# Capacitive-Fluid-Level-Sensor-schematic.net
KiCad netlist of a schematic drawn in EasyEDA Pro
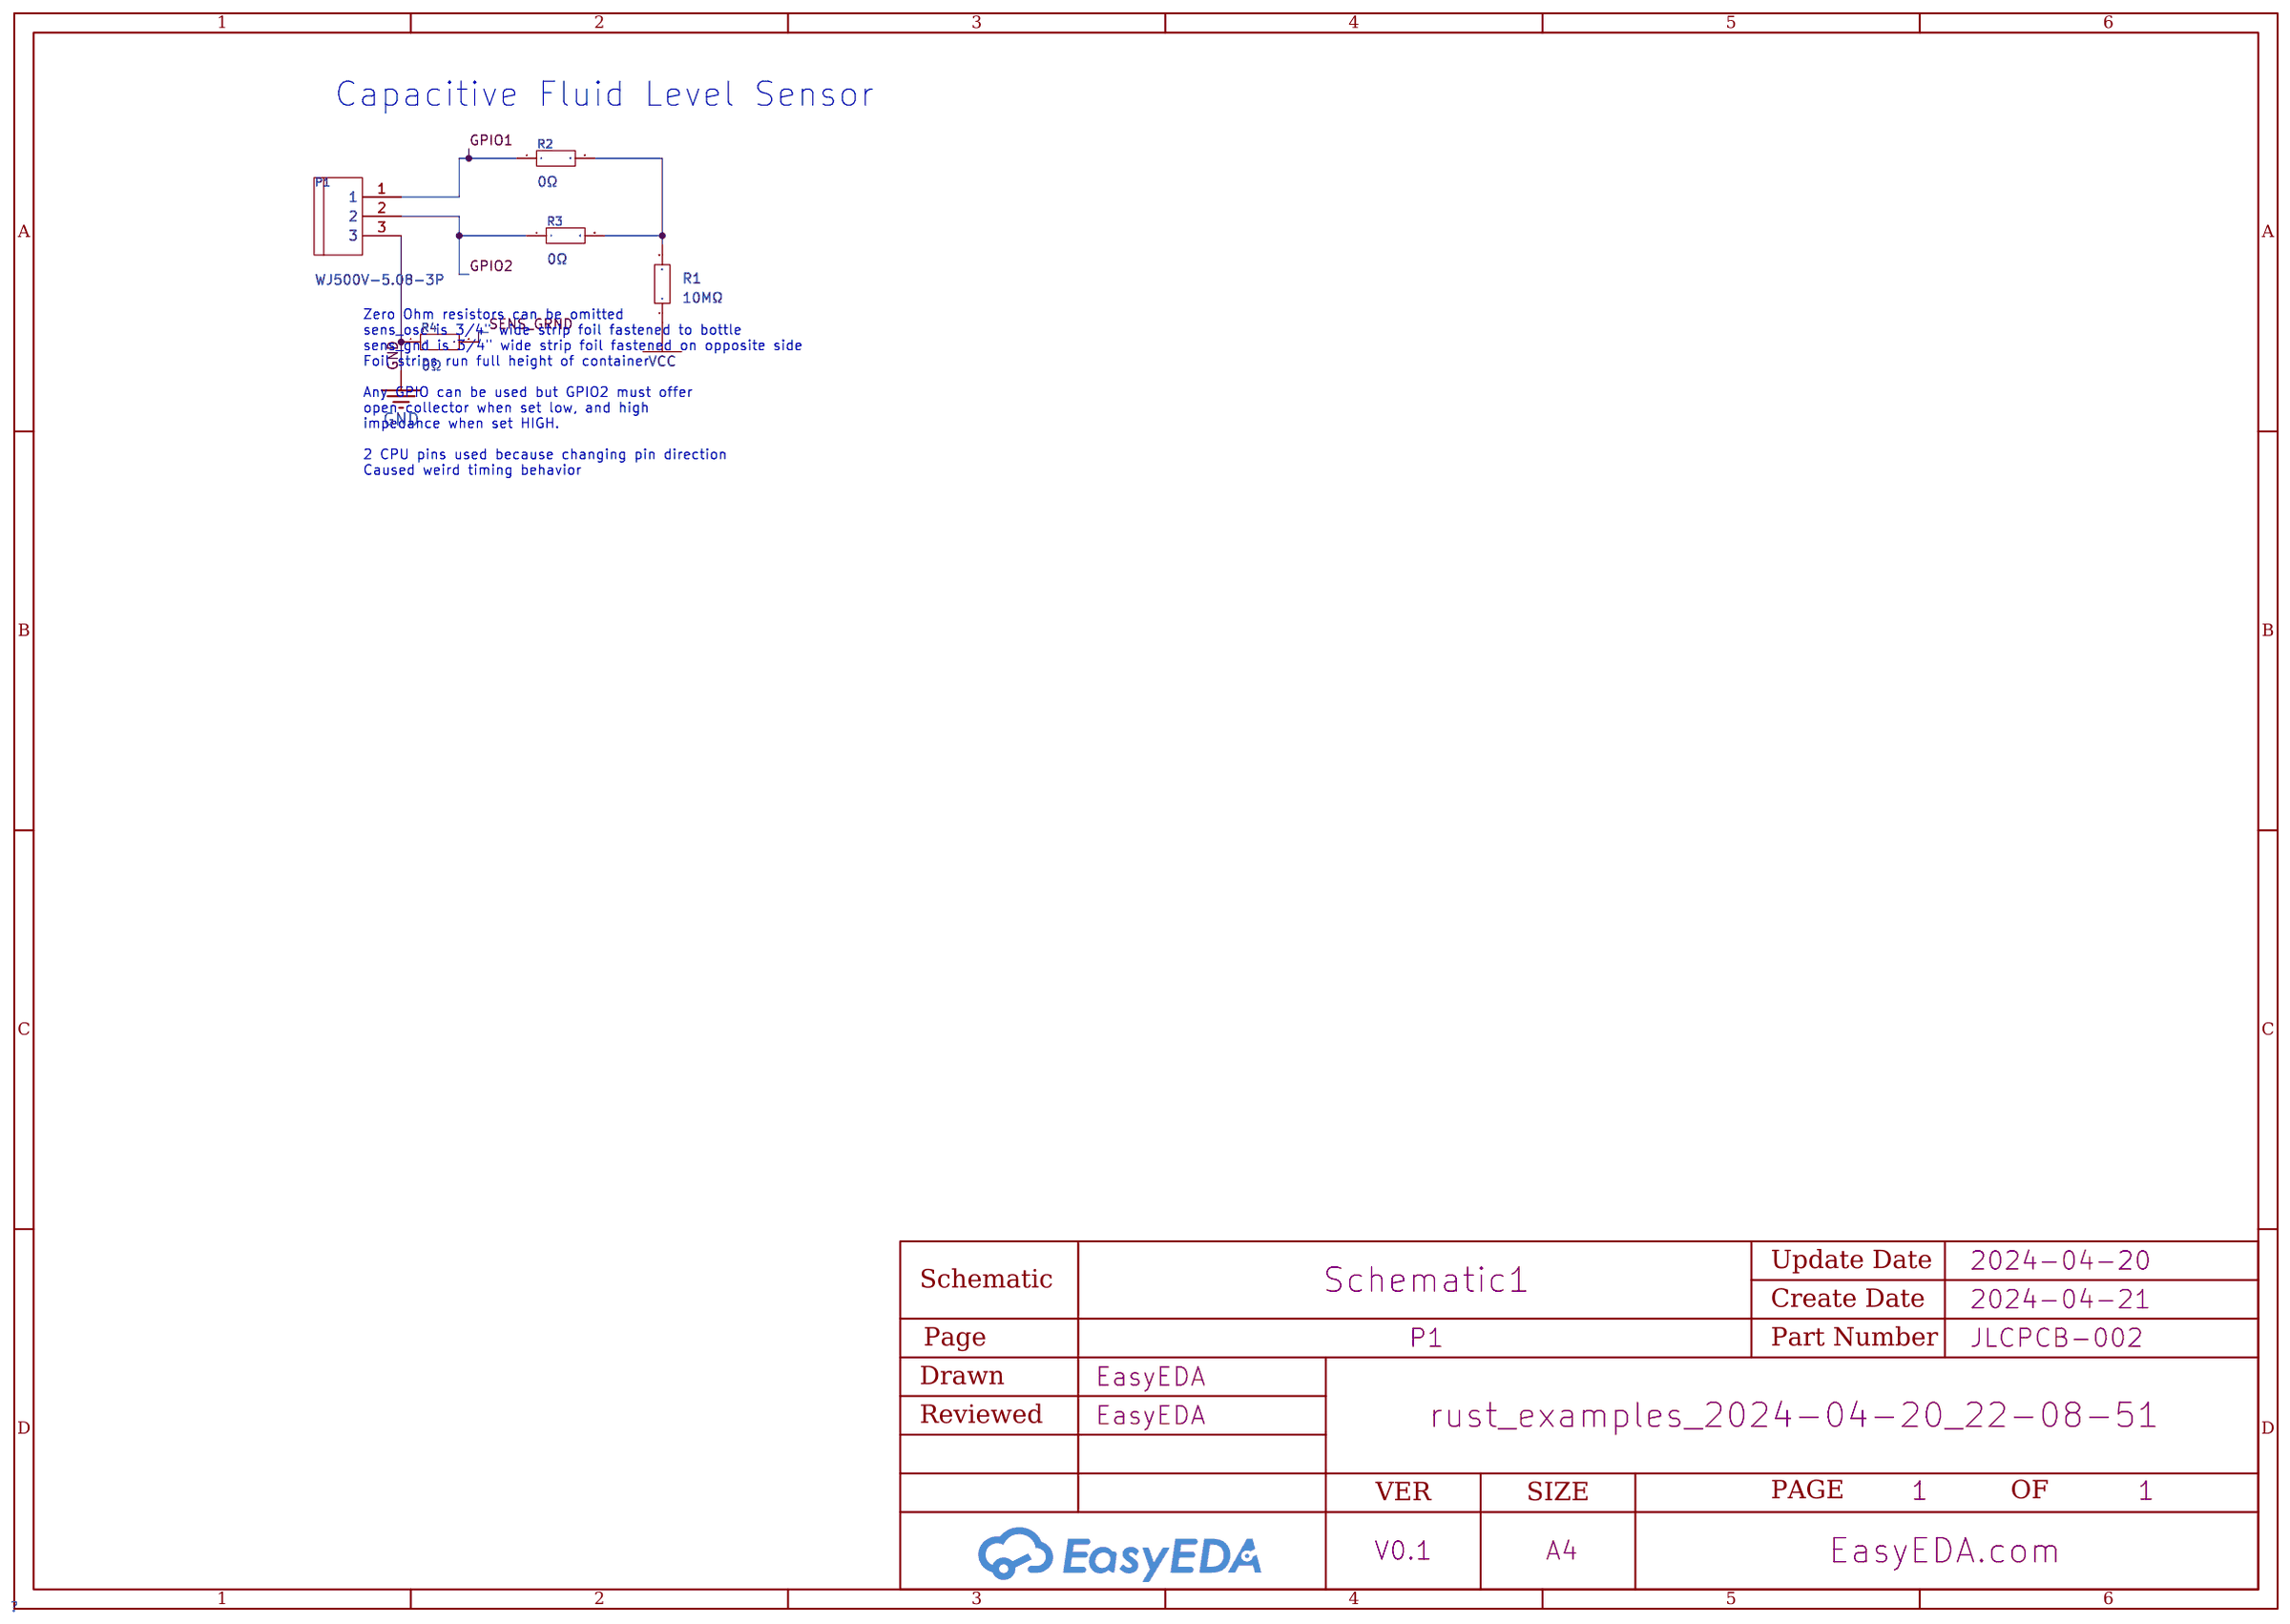
[diagram p0: schematic sheet]

(export (version "E")
  (design (tool "Eeschema 10.0.6"))
  (components
    (comp (ref "P1")
      (value "WJ500V-5.08-3P")
      (footprint "easyedapro:CONN-TH_3P-P5.00_WJ500V-5.08-3P")
      (fields (field (name "Manufacturer") "KANGNEX(康奈克斯电气)"))
      (libsource (lib "easyedapro") (part "WJ500V-5.08-3P-14-00A"))
    )
    (comp (ref "R1")
      (value "10MΩ")
      (footprint "easyedapro:R0805")
      (fields
        (field (name "Manufacturer Part") "0805W8F1005T5E")
        (field (name "Manufacturer") "UNI-ROYAL(厚声)")
      )
      (libsource (lib "easyedapro") (part "0805W8F1005T5E"))
    )
    (comp (ref "R2")
      (value "0Ω")
      (footprint "easyedapro:R0805")
      (fields
        (field (name "Manufacturer Part") "0805W8F0000T5E")
        (field (name "Manufacturer") "UNI-ROYAL(厚声)")
      )
      (libsource (lib "easyedapro") (part "0805W8F0000T5E"))
    )
    (comp (ref "R3")
      (value "0Ω")
      (footprint "easyedapro:R0805")
      (fields
        (field (name "Manufacturer Part") "0805W8F0000T5E")
        (field (name "Manufacturer") "UNI-ROYAL(厚声)")
      )
      (libsource (lib "easyedapro") (part "0805W8F0000T5E"))
    )
    (comp (ref "R4")
      (value "0Ω")
      (footprint "easyedapro:R0805")
      (fields
        (field (name "Manufacturer Part") "0805W8F0000T5E")
        (field (name "Manufacturer") "UNI-ROYAL(厚声)")
      )
      (libsource (lib "easyedapro") (part "0805W8F0000T5E"))
    )
  )
  (nets
    (net (code "1") (name "/GPIO1") (class "Default")
      (node (ref "P1") (pin "1") (pinfunction "1_1") (pintype "input"))
      (node (ref "R2") (pin "1") (pinfunction "1_1") (pintype "input"))
    )
    (net (code "2") (name "/GPIO2") (class "Default")
      (node (ref "P1") (pin "2") (pinfunction "2_2") (pintype "input"))
      (node (ref "R3") (pin "1") (pinfunction "1_1") (pintype "input"))
    )
    (net (code "3") (name "/SENS_GRND") (class "Default")
      (node (ref "R4") (pin "2") (pinfunction "2_2") (pintype "input"))
    )
    (net (code "4") (name "GND") (class "Default")
      (node (ref "P1") (pin "3") (pinfunction "3_3") (pintype "input"))
      (node (ref "R4") (pin "1") (pinfunction "1_1") (pintype "input"))
    )
    (net (code "5") (name "Net-(R1-Pad2)") (class "Default")
      (node (ref "R1") (pin "2") (pinfunction "2_2") (pintype "input"))
      (node (ref "R2") (pin "2") (pinfunction "2_2") (pintype "input"))
      (node (ref "R3") (pin "2") (pinfunction "2_2") (pintype "input"))
    )
    (net (code "6") (name "VCC") (class "Default")
      (node (ref "R1") (pin "1") (pinfunction "1_1") (pintype "input"))
    )
  )
)
